# AstableMultivibrator-PNP-alt.net
KiCad netlist of a schematic drawn in EAGLE
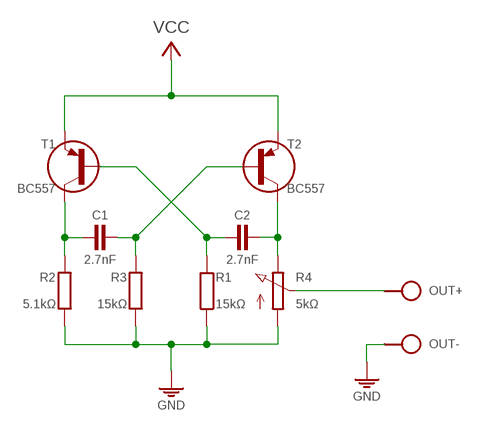
[diagram p0: schematic, sheet 1]

(export (version "E")
  (design (tool "Eeschema 10.0.6"))
  (components
    (comp (ref "C1")
      (value "2.7nF")
      (footprint "eagle-import:C0750-020X044")
      (libsource (lib "eagle-import") (part "C-H075-020X044"))
    )
    (comp (ref "C2")
      (value "2.7nF")
      (footprint "eagle-import:C0750-020X044")
      (libsource (lib "eagle-import") (part "C-H075-020X044"))
    )
    (comp (ref "J1")
      (value "VCC_GNDPWR-L")
      (footprint "eagle-import:PWR-L")
      (libsource (lib "eagle-import") (part "VCC_GNDPWR-L"))
    )
    (comp (ref "OUT")
      (value "SPAD+-+-")
      (footprint "eagle-import:SPAD+-")
      (libsource (lib "eagle-import") (part "SPAD+-+-"))
    )
    (comp (ref "R1")
      (value "15kΩ")
      (footprint "eagle-import:0202_7-V")
      (libsource (lib "eagle-import") (part "R0202/7-V"))
    )
    (comp (ref "R2")
      (value "5.1kΩ")
      (footprint "eagle-import:0202_7-V")
      (libsource (lib "eagle-import") (part "R0202/7-V"))
    )
    (comp (ref "R3")
      (value "15kΩ")
      (footprint "eagle-import:0202_7-V")
      (libsource (lib "eagle-import") (part "R0202/7-V"))
    )
    (comp (ref "R4")
      (value "5kΩ")
      (footprint "eagle-import:POT-V")
      (libsource (lib "eagle-import") (part "POT-V"))
    )
    (comp (ref "T1")
      (value "BC557")
      (footprint "eagle-import:TO92-CBE")
      (libsource (lib "eagle-import") (part "BC557CBE"))
    )
    (comp (ref "T2")
      (value "BC557")
      (footprint "eagle-import:TO92-CBE")
      (libsource (lib "eagle-import") (part "BC557CBE"))
    )
  )
  (nets
    (net (code "1") (name "GND") (class "Default")
      (node (ref "J1") (pin "1") (pinfunction "GND_1") (pintype "power_in"))
      (node (ref "OUT") (pin "1") (pinfunction "P$1_1") (pintype "passive"))
      (node (ref "R1") (pin "1") (pinfunction "2_1") (pintype "passive"))
      (node (ref "R2") (pin "1") (pinfunction "2_1") (pintype "passive"))
      (node (ref "R3") (pin "1") (pinfunction "2_1") (pintype "passive"))
      (node (ref "R4") (pin "A") (pinfunction "A_A") (pintype "passive"))
    )
    (net (code "2") (name "Net-(C2-Pad2)") (class "Default")
      (node (ref "C2") (pin "2") (pinfunction "2_2") (pintype "passive"))
      (node (ref "R4") (pin "E") (pinfunction "E_E") (pintype "passive"))
      (node (ref "T2") (pin "C") (pinfunction "C_C") (pintype "passive"))
    )
    (net (code "3") (name "Net-(J1A-VCC)") (class "Default")
      (node (ref "J1") (pin "2") (pinfunction "VCC_2") (pintype "power_in"))
      (node (ref "T1") (pin "E") (pinfunction "E_E") (pintype "passive"))
      (node (ref "T2") (pin "E") (pinfunction "E_E") (pintype "passive"))
    )
    (net (code "4") (name "Net-(OUTA-P$1)") (class "Default")
      (node (ref "OUT") (pin "2") (pinfunction "P$1_2") (pintype "passive"))
      (node (ref "R4") (pin "S") (pinfunction "S_S") (pintype "passive"))
    )
    (net (code "5") (name "Net-(R1-1)") (class "Default")
      (node (ref "C2") (pin "1") (pinfunction "1_1") (pintype "passive"))
      (node (ref "R1") (pin "2") (pinfunction "1_2") (pintype "passive"))
      (node (ref "T1") (pin "B") (pinfunction "B_B") (pintype "passive"))
    )
    (net (code "6") (name "Net-(R2-1)") (class "Default")
      (node (ref "C1") (pin "1") (pinfunction "1_1") (pintype "passive"))
      (node (ref "R2") (pin "2") (pinfunction "1_2") (pintype "passive"))
      (node (ref "T1") (pin "C") (pinfunction "C_C") (pintype "passive"))
    )
    (net (code "7") (name "Net-(R3-1)") (class "Default")
      (node (ref "C1") (pin "2") (pinfunction "2_2") (pintype "passive"))
      (node (ref "R3") (pin "2") (pinfunction "1_2") (pintype "passive"))
      (node (ref "T2") (pin "B") (pinfunction "B_B") (pintype "passive"))
    )
  )
)
